# SCH_TH_RGB_LED_Stick_2022-05-16.net
KiCad netlist of a schematic drawn in EasyEDA
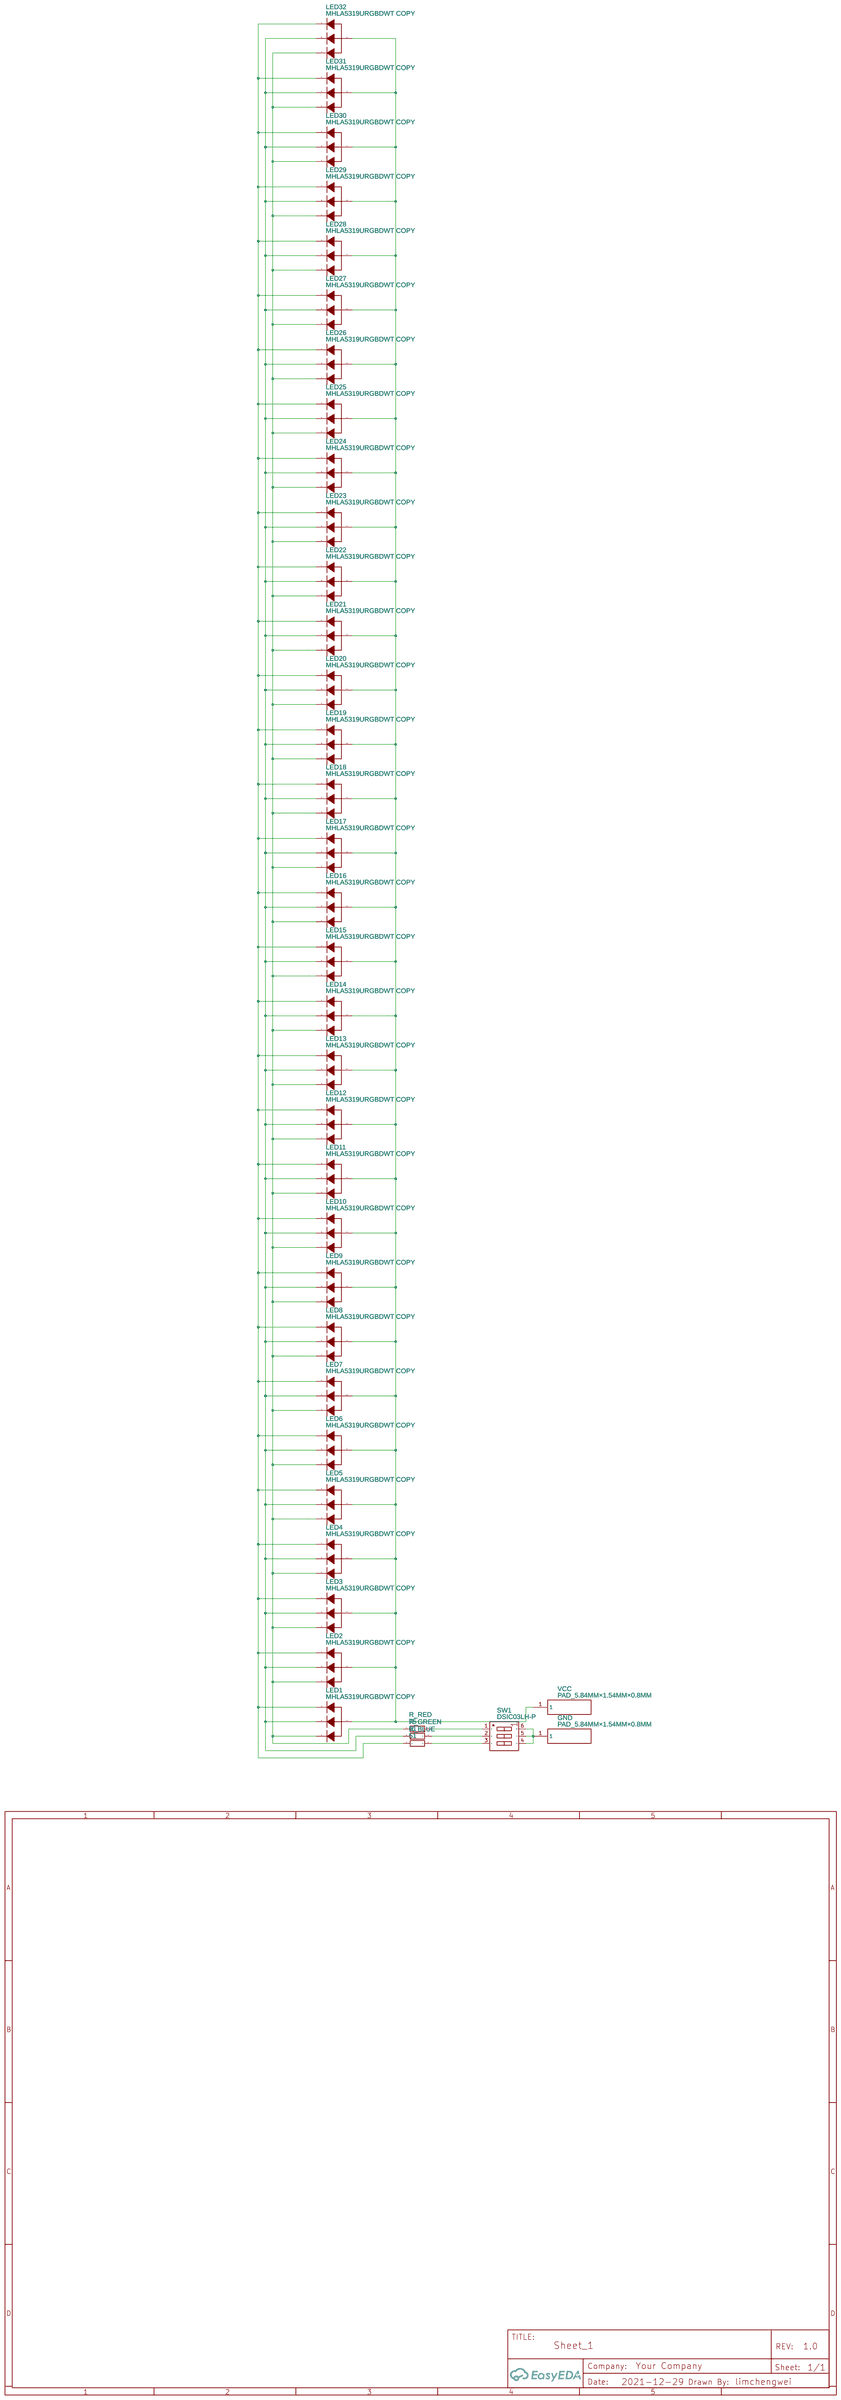
[diagram p0: schematic sheet]

(export (version "E")
  (design (tool "Eeschema 10.0.6"))
  (components
    (comp (ref "GND")
      (value "PAD_5.84MM×1.54MM×0.8MM")
      (fields
        (field (name "BOM_Manufacturer Part") "PAD_5.84mm×1.54mm×0.8mm")
        (field (name "BOM_Supplier Part") "C9900000335")
      )
      (libsource (lib "") (part "PAD_5.84MM×1.54MM×0.8MM_1"))
    )
    (comp (ref "LED1")
      (value "MHLA5319URGBDWT COPY")
      (fields
        (field (name "BOM_Manufacturer Part") "MHLA5319URGBDWT")
        (field (name "BOM_Supplier Part") "C417349")
      )
      (libsource (lib "") (part "MHLA5319URGBDWT COPY"))
    )
    (comp (ref "LED2")
      (value "MHLA5319URGBDWT COPY")
      (fields
        (field (name "BOM_Manufacturer Part") "MHLA5319URGBDWT")
        (field (name "BOM_Supplier Part") "C417349")
      )
      (libsource (lib "") (part "MHLA5319URGBDWT COPY"))
    )
    (comp (ref "LED3")
      (value "MHLA5319URGBDWT COPY")
      (fields
        (field (name "BOM_Manufacturer Part") "MHLA5319URGBDWT")
        (field (name "BOM_Supplier Part") "C417349")
      )
      (libsource (lib "") (part "MHLA5319URGBDWT COPY"))
    )
    (comp (ref "LED4")
      (value "MHLA5319URGBDWT COPY")
      (fields
        (field (name "BOM_Manufacturer Part") "MHLA5319URGBDWT")
        (field (name "BOM_Supplier Part") "C417349")
      )
      (libsource (lib "") (part "MHLA5319URGBDWT COPY"))
    )
    (comp (ref "LED5")
      (value "MHLA5319URGBDWT COPY")
      (fields
        (field (name "BOM_Manufacturer Part") "MHLA5319URGBDWT")
        (field (name "BOM_Supplier Part") "C417349")
      )
      (libsource (lib "") (part "MHLA5319URGBDWT COPY"))
    )
    (comp (ref "LED6")
      (value "MHLA5319URGBDWT COPY")
      (fields
        (field (name "BOM_Manufacturer Part") "MHLA5319URGBDWT")
        (field (name "BOM_Supplier Part") "C417349")
      )
      (libsource (lib "") (part "MHLA5319URGBDWT COPY"))
    )
    (comp (ref "LED7")
      (value "MHLA5319URGBDWT COPY")
      (fields
        (field (name "BOM_Manufacturer Part") "MHLA5319URGBDWT")
        (field (name "BOM_Supplier Part") "C417349")
      )
      (libsource (lib "") (part "MHLA5319URGBDWT COPY"))
    )
    (comp (ref "LED8")
      (value "MHLA5319URGBDWT COPY")
      (fields
        (field (name "BOM_Manufacturer Part") "MHLA5319URGBDWT")
        (field (name "BOM_Supplier Part") "C417349")
      )
      (libsource (lib "") (part "MHLA5319URGBDWT COPY"))
    )
    (comp (ref "LED9")
      (value "MHLA5319URGBDWT COPY")
      (fields
        (field (name "BOM_Manufacturer Part") "MHLA5319URGBDWT")
        (field (name "BOM_Supplier Part") "C417349")
      )
      (libsource (lib "") (part "MHLA5319URGBDWT COPY"))
    )
    (comp (ref "LED10")
      (value "MHLA5319URGBDWT COPY")
      (fields
        (field (name "BOM_Manufacturer Part") "MHLA5319URGBDWT")
        (field (name "BOM_Supplier Part") "C417349")
      )
      (libsource (lib "") (part "MHLA5319URGBDWT COPY"))
    )
    (comp (ref "LED11")
      (value "MHLA5319URGBDWT COPY")
      (fields
        (field (name "BOM_Manufacturer Part") "MHLA5319URGBDWT")
        (field (name "BOM_Supplier Part") "C417349")
      )
      (libsource (lib "") (part "MHLA5319URGBDWT COPY"))
    )
    (comp (ref "LED12")
      (value "MHLA5319URGBDWT COPY")
      (fields
        (field (name "BOM_Manufacturer Part") "MHLA5319URGBDWT")
        (field (name "BOM_Supplier Part") "C417349")
      )
      (libsource (lib "") (part "MHLA5319URGBDWT COPY"))
    )
    (comp (ref "LED13")
      (value "MHLA5319URGBDWT COPY")
      (fields
        (field (name "BOM_Manufacturer Part") "MHLA5319URGBDWT")
        (field (name "BOM_Supplier Part") "C417349")
      )
      (libsource (lib "") (part "MHLA5319URGBDWT COPY"))
    )
    (comp (ref "LED14")
      (value "MHLA5319URGBDWT COPY")
      (fields
        (field (name "BOM_Manufacturer Part") "MHLA5319URGBDWT")
        (field (name "BOM_Supplier Part") "C417349")
      )
      (libsource (lib "") (part "MHLA5319URGBDWT COPY"))
    )
    (comp (ref "LED15")
      (value "MHLA5319URGBDWT COPY")
      (fields
        (field (name "BOM_Manufacturer Part") "MHLA5319URGBDWT")
        (field (name "BOM_Supplier Part") "C417349")
      )
      (libsource (lib "") (part "MHLA5319URGBDWT COPY"))
    )
    (comp (ref "LED16")
      (value "MHLA5319URGBDWT COPY")
      (fields
        (field (name "BOM_Manufacturer Part") "MHLA5319URGBDWT")
        (field (name "BOM_Supplier Part") "C417349")
      )
      (libsource (lib "") (part "MHLA5319URGBDWT COPY"))
    )
    (comp (ref "LED17")
      (value "MHLA5319URGBDWT COPY")
      (fields
        (field (name "BOM_Manufacturer Part") "MHLA5319URGBDWT")
        (field (name "BOM_Supplier Part") "C417349")
      )
      (libsource (lib "") (part "MHLA5319URGBDWT COPY"))
    )
    (comp (ref "LED18")
      (value "MHLA5319URGBDWT COPY")
      (fields
        (field (name "BOM_Manufacturer Part") "MHLA5319URGBDWT")
        (field (name "BOM_Supplier Part") "C417349")
      )
      (libsource (lib "") (part "MHLA5319URGBDWT COPY"))
    )
    (comp (ref "LED19")
      (value "MHLA5319URGBDWT COPY")
      (fields
        (field (name "BOM_Manufacturer Part") "MHLA5319URGBDWT")
        (field (name "BOM_Supplier Part") "C417349")
      )
      (libsource (lib "") (part "MHLA5319URGBDWT COPY"))
    )
    (comp (ref "LED20")
      (value "MHLA5319URGBDWT COPY")
      (fields
        (field (name "BOM_Manufacturer Part") "MHLA5319URGBDWT")
        (field (name "BOM_Supplier Part") "C417349")
      )
      (libsource (lib "") (part "MHLA5319URGBDWT COPY"))
    )
    (comp (ref "LED21")
      (value "MHLA5319URGBDWT COPY")
      (fields
        (field (name "BOM_Manufacturer Part") "MHLA5319URGBDWT")
        (field (name "BOM_Supplier Part") "C417349")
      )
      (libsource (lib "") (part "MHLA5319URGBDWT COPY"))
    )
    (comp (ref "LED22")
      (value "MHLA5319URGBDWT COPY")
      (fields
        (field (name "BOM_Manufacturer Part") "MHLA5319URGBDWT")
        (field (name "BOM_Supplier Part") "C417349")
      )
      (libsource (lib "") (part "MHLA5319URGBDWT COPY"))
    )
    (comp (ref "LED23")
      (value "MHLA5319URGBDWT COPY")
      (fields
        (field (name "BOM_Manufacturer Part") "MHLA5319URGBDWT")
        (field (name "BOM_Supplier Part") "C417349")
      )
      (libsource (lib "") (part "MHLA5319URGBDWT COPY"))
    )
    (comp (ref "LED24")
      (value "MHLA5319URGBDWT COPY")
      (fields
        (field (name "BOM_Manufacturer Part") "MHLA5319URGBDWT")
        (field (name "BOM_Supplier Part") "C417349")
      )
      (libsource (lib "") (part "MHLA5319URGBDWT COPY"))
    )
    (comp (ref "LED25")
      (value "MHLA5319URGBDWT COPY")
      (fields
        (field (name "BOM_Manufacturer Part") "MHLA5319URGBDWT")
        (field (name "BOM_Supplier Part") "C417349")
      )
      (libsource (lib "") (part "MHLA5319URGBDWT COPY"))
    )
    (comp (ref "LED26")
      (value "MHLA5319URGBDWT COPY")
      (fields
        (field (name "BOM_Manufacturer Part") "MHLA5319URGBDWT")
        (field (name "BOM_Supplier Part") "C417349")
      )
      (libsource (lib "") (part "MHLA5319URGBDWT COPY"))
    )
    (comp (ref "LED27")
      (value "MHLA5319URGBDWT COPY")
      (fields
        (field (name "BOM_Manufacturer Part") "MHLA5319URGBDWT")
        (field (name "BOM_Supplier Part") "C417349")
      )
      (libsource (lib "") (part "MHLA5319URGBDWT COPY"))
    )
    (comp (ref "LED28")
      (value "MHLA5319URGBDWT COPY")
      (fields
        (field (name "BOM_Manufacturer Part") "MHLA5319URGBDWT")
        (field (name "BOM_Supplier Part") "C417349")
      )
      (libsource (lib "") (part "MHLA5319URGBDWT COPY"))
    )
    (comp (ref "LED29")
      (value "MHLA5319URGBDWT COPY")
      (fields
        (field (name "BOM_Manufacturer Part") "MHLA5319URGBDWT")
        (field (name "BOM_Supplier Part") "C417349")
      )
      (libsource (lib "") (part "MHLA5319URGBDWT COPY"))
    )
    (comp (ref "LED30")
      (value "MHLA5319URGBDWT COPY")
      (fields
        (field (name "BOM_Manufacturer Part") "MHLA5319URGBDWT")
        (field (name "BOM_Supplier Part") "C417349")
      )
      (libsource (lib "") (part "MHLA5319URGBDWT COPY"))
    )
    (comp (ref "LED31")
      (value "MHLA5319URGBDWT COPY")
      (fields
        (field (name "BOM_Manufacturer Part") "MHLA5319URGBDWT")
        (field (name "BOM_Supplier Part") "C417349")
      )
      (libsource (lib "") (part "MHLA5319URGBDWT COPY"))
    )
    (comp (ref "LED32")
      (value "MHLA5319URGBDWT COPY")
      (fields
        (field (name "BOM_Manufacturer Part") "MHLA5319URGBDWT")
        (field (name "BOM_Supplier Part") "C417349")
      )
      (libsource (lib "") (part "MHLA5319URGBDWT COPY"))
    )
    (comp (ref "R_BLUE")
      (value "51")
      (fields (field (name "BOM_Supplier Part") "C119319"))
      (libsource (lib "") (part "MF1/4W-620Ω±1% T52_2"))
    )
    (comp (ref "R_GREEN")
      (value "51")
      (fields (field (name "BOM_Supplier Part") "C119319"))
      (libsource (lib "") (part "MF1/4W-620Ω±1% T52"))
    )
    (comp (ref "R_RED")
      (value "75")
      (fields (field (name "BOM_Supplier Part") "C119319"))
      (libsource (lib "") (part "MF1/4W-620Ω±1% T52_1"))
    )
    (comp (ref "SW1")
      (value "DSIC03LH-P")
      (fields (field (name "BOM_Supplier Part") "C319041"))
      (libsource (lib "") (part "DSIC03LH-P"))
    )
    (comp (ref "VCC")
      (value "PAD_5.84MM×1.54MM×0.8MM")
      (fields
        (field (name "BOM_Manufacturer Part") "PAD_5.84mm×1.54mm×0.8mm")
        (field (name "BOM_Supplier Part") "C9900000335")
      )
      (libsource (lib "") (part "PAD_5.84MM×1.54MM×0.8MM"))
    )
  )
  (nets
    (net (code "1") (name "Net-(LED1-+)") (class "Default")
      (node (ref "LED1") (pin "2") (pinfunction "+_2") (pintype "unspecified"))
      (node (ref "LED10") (pin "2") (pinfunction "+_2") (pintype "unspecified"))
      (node (ref "LED11") (pin "2") (pinfunction "+_2") (pintype "unspecified"))
      (node (ref "LED12") (pin "2") (pinfunction "+_2") (pintype "unspecified"))
      (node (ref "LED13") (pin "2") (pinfunction "+_2") (pintype "unspecified"))
      (node (ref "LED14") (pin "2") (pinfunction "+_2") (pintype "unspecified"))
      (node (ref "LED15") (pin "2") (pinfunction "+_2") (pintype "unspecified"))
      (node (ref "LED16") (pin "2") (pinfunction "+_2") (pintype "unspecified"))
      (node (ref "LED17") (pin "2") (pinfunction "+_2") (pintype "unspecified"))
      (node (ref "LED18") (pin "2") (pinfunction "+_2") (pintype "unspecified"))
      (node (ref "LED19") (pin "2") (pinfunction "+_2") (pintype "unspecified"))
      (node (ref "LED2") (pin "2") (pinfunction "+_2") (pintype "unspecified"))
      (node (ref "LED20") (pin "2") (pinfunction "+_2") (pintype "unspecified"))
      (node (ref "LED21") (pin "2") (pinfunction "+_2") (pintype "unspecified"))
      (node (ref "LED22") (pin "2") (pinfunction "+_2") (pintype "unspecified"))
      (node (ref "LED23") (pin "2") (pinfunction "+_2") (pintype "unspecified"))
      (node (ref "LED24") (pin "2") (pinfunction "+_2") (pintype "unspecified"))
      (node (ref "LED25") (pin "2") (pinfunction "+_2") (pintype "unspecified"))
      (node (ref "LED26") (pin "2") (pinfunction "+_2") (pintype "unspecified"))
      (node (ref "LED27") (pin "2") (pinfunction "+_2") (pintype "unspecified"))
      (node (ref "LED28") (pin "2") (pinfunction "+_2") (pintype "unspecified"))
      (node (ref "LED29") (pin "2") (pinfunction "+_2") (pintype "unspecified"))
      (node (ref "LED3") (pin "2") (pinfunction "+_2") (pintype "unspecified"))
      (node (ref "LED30") (pin "2") (pinfunction "+_2") (pintype "unspecified"))
      (node (ref "LED31") (pin "2") (pinfunction "+_2") (pintype "unspecified"))
      (node (ref "LED32") (pin "2") (pinfunction "+_2") (pintype "unspecified"))
      (node (ref "LED4") (pin "2") (pinfunction "+_2") (pintype "unspecified"))
      (node (ref "LED5") (pin "2") (pinfunction "+_2") (pintype "unspecified"))
      (node (ref "LED6") (pin "2") (pinfunction "+_2") (pintype "unspecified"))
      (node (ref "LED7") (pin "2") (pinfunction "+_2") (pintype "unspecified"))
      (node (ref "LED8") (pin "2") (pinfunction "+_2") (pintype "unspecified"))
      (node (ref "LED9") (pin "2") (pinfunction "+_2") (pintype "unspecified"))
      (node (ref "VCC") (pin "1") (pinfunction "1_1") (pintype "unspecified"))
    )
    (net (code "2") (name "Net-(LED1---Pad1)") (class "Default")
      (node (ref "LED1") (pin "1") (pinfunction "-_1") (pintype "unspecified"))
      (node (ref "LED10") (pin "1") (pinfunction "-_1") (pintype "unspecified"))
      (node (ref "LED11") (pin "1") (pinfunction "-_1") (pintype "unspecified"))
      (node (ref "LED12") (pin "1") (pinfunction "-_1") (pintype "unspecified"))
      (node (ref "LED13") (pin "1") (pinfunction "-_1") (pintype "unspecified"))
      (node (ref "LED14") (pin "1") (pinfunction "-_1") (pintype "unspecified"))
      (node (ref "LED15") (pin "1") (pinfunction "-_1") (pintype "unspecified"))
      (node (ref "LED16") (pin "1") (pinfunction "-_1") (pintype "unspecified"))
      (node (ref "LED17") (pin "1") (pinfunction "-_1") (pintype "unspecified"))
      (node (ref "LED18") (pin "1") (pinfunction "-_1") (pintype "unspecified"))
      (node (ref "LED19") (pin "1") (pinfunction "-_1") (pintype "unspecified"))
      (node (ref "LED2") (pin "1") (pinfunction "-_1") (pintype "unspecified"))
      (node (ref "LED20") (pin "1") (pinfunction "-_1") (pintype "unspecified"))
      (node (ref "LED21") (pin "1") (pinfunction "-_1") (pintype "unspecified"))
      (node (ref "LED22") (pin "1") (pinfunction "-_1") (pintype "unspecified"))
      (node (ref "LED23") (pin "1") (pinfunction "-_1") (pintype "unspecified"))
      (node (ref "LED24") (pin "1") (pinfunction "-_1") (pintype "unspecified"))
      (node (ref "LED25") (pin "1") (pinfunction "-_1") (pintype "unspecified"))
      (node (ref "LED26") (pin "1") (pinfunction "-_1") (pintype "unspecified"))
      (node (ref "LED27") (pin "1") (pinfunction "-_1") (pintype "unspecified"))
      (node (ref "LED28") (pin "1") (pinfunction "-_1") (pintype "unspecified"))
      (node (ref "LED29") (pin "1") (pinfunction "-_1") (pintype "unspecified"))
      (node (ref "LED3") (pin "1") (pinfunction "-_1") (pintype "unspecified"))
      (node (ref "LED30") (pin "1") (pinfunction "-_1") (pintype "unspecified"))
      (node (ref "LED31") (pin "1") (pinfunction "-_1") (pintype "unspecified"))
      (node (ref "LED32") (pin "1") (pinfunction "-_1") (pintype "unspecified"))
      (node (ref "LED4") (pin "1") (pinfunction "-_1") (pintype "unspecified"))
      (node (ref "LED5") (pin "1") (pinfunction "-_1") (pintype "unspecified"))
      (node (ref "LED6") (pin "1") (pinfunction "-_1") (pintype "unspecified"))
      (node (ref "LED7") (pin "1") (pinfunction "-_1") (pintype "unspecified"))
      (node (ref "LED8") (pin "1") (pinfunction "-_1") (pintype "unspecified"))
      (node (ref "LED9") (pin "1") (pinfunction "-_1") (pintype "unspecified"))
      (node (ref "R_RED") (pin "2") (pinfunction "2_2") (pintype "unspecified"))
    )
    (net (code "3") (name "Net-(LED1---Pad3)") (class "Default")
      (node (ref "LED1") (pin "3") (pinfunction "-_3") (pintype "unspecified"))
      (node (ref "LED10") (pin "3") (pinfunction "-_3") (pintype "unspecified"))
      (node (ref "LED11") (pin "3") (pinfunction "-_3") (pintype "unspecified"))
      (node (ref "LED12") (pin "3") (pinfunction "-_3") (pintype "unspecified"))
      (node (ref "LED13") (pin "3") (pinfunction "-_3") (pintype "unspecified"))
      (node (ref "LED14") (pin "3") (pinfunction "-_3") (pintype "unspecified"))
      (node (ref "LED15") (pin "3") (pinfunction "-_3") (pintype "unspecified"))
      (node (ref "LED16") (pin "3") (pinfunction "-_3") (pintype "unspecified"))
      (node (ref "LED17") (pin "3") (pinfunction "-_3") (pintype "unspecified"))
      (node (ref "LED18") (pin "3") (pinfunction "-_3") (pintype "unspecified"))
      (node (ref "LED19") (pin "3") (pinfunction "-_3") (pintype "unspecified"))
      (node (ref "LED2") (pin "3") (pinfunction "-_3") (pintype "unspecified"))
      (node (ref "LED20") (pin "3") (pinfunction "-_3") (pintype "unspecified"))
      (node (ref "LED21") (pin "3") (pinfunction "-_3") (pintype "unspecified"))
      (node (ref "LED22") (pin "3") (pinfunction "-_3") (pintype "unspecified"))
      (node (ref "LED23") (pin "3") (pinfunction "-_3") (pintype "unspecified"))
      (node (ref "LED24") (pin "3") (pinfunction "-_3") (pintype "unspecified"))
      (node (ref "LED25") (pin "3") (pinfunction "-_3") (pintype "unspecified"))
      (node (ref "LED26") (pin "3") (pinfunction "-_3") (pintype "unspecified"))
      (node (ref "LED27") (pin "3") (pinfunction "-_3") (pintype "unspecified"))
      (node (ref "LED28") (pin "3") (pinfunction "-_3") (pintype "unspecified"))
      (node (ref "LED29") (pin "3") (pinfunction "-_3") (pintype "unspecified"))
      (node (ref "LED3") (pin "3") (pinfunction "-_3") (pintype "unspecified"))
      (node (ref "LED30") (pin "3") (pinfunction "-_3") (pintype "unspecified"))
      (node (ref "LED31") (pin "3") (pinfunction "-_3") (pintype "unspecified"))
      (node (ref "LED32") (pin "3") (pinfunction "-_3") (pintype "unspecified"))
      (node (ref "LED4") (pin "3") (pinfunction "-_3") (pintype "unspecified"))
      (node (ref "LED5") (pin "3") (pinfunction "-_3") (pintype "unspecified"))
      (node (ref "LED6") (pin "3") (pinfunction "-_3") (pintype "unspecified"))
      (node (ref "LED7") (pin "3") (pinfunction "-_3") (pintype "unspecified"))
      (node (ref "LED8") (pin "3") (pinfunction "-_3") (pintype "unspecified"))
      (node (ref "LED9") (pin "3") (pinfunction "-_3") (pintype "unspecified"))
      (node (ref "R_GREEN") (pin "2") (pinfunction "2_2") (pintype "unspecified"))
    )
    (net (code "4") (name "Net-(LED1---Pad4)") (class "Default")
      (node (ref "LED1") (pin "4") (pinfunction "-_4") (pintype "unspecified"))
      (node (ref "LED10") (pin "4") (pinfunction "-_4") (pintype "unspecified"))
      (node (ref "LED11") (pin "4") (pinfunction "-_4") (pintype "unspecified"))
      (node (ref "LED12") (pin "4") (pinfunction "-_4") (pintype "unspecified"))
      (node (ref "LED13") (pin "4") (pinfunction "-_4") (pintype "unspecified"))
      (node (ref "LED14") (pin "4") (pinfunction "-_4") (pintype "unspecified"))
      (node (ref "LED15") (pin "4") (pinfunction "-_4") (pintype "unspecified"))
      (node (ref "LED16") (pin "4") (pinfunction "-_4") (pintype "unspecified"))
      (node (ref "LED17") (pin "4") (pinfunction "-_4") (pintype "unspecified"))
      (node (ref "LED18") (pin "4") (pinfunction "-_4") (pintype "unspecified"))
      (node (ref "LED19") (pin "4") (pinfunction "-_4") (pintype "unspecified"))
      (node (ref "LED2") (pin "4") (pinfunction "-_4") (pintype "unspecified"))
      (node (ref "LED20") (pin "4") (pinfunction "-_4") (pintype "unspecified"))
      (node (ref "LED21") (pin "4") (pinfunction "-_4") (pintype "unspecified"))
      (node (ref "LED22") (pin "4") (pinfunction "-_4") (pintype "unspecified"))
      (node (ref "LED23") (pin "4") (pinfunction "-_4") (pintype "unspecified"))
      (node (ref "LED24") (pin "4") (pinfunction "-_4") (pintype "unspecified"))
      (node (ref "LED25") (pin "4") (pinfunction "-_4") (pintype "unspecified"))
      (node (ref "LED26") (pin "4") (pinfunction "-_4") (pintype "unspecified"))
      (node (ref "LED27") (pin "4") (pinfunction "-_4") (pintype "unspecified"))
      (node (ref "LED28") (pin "4") (pinfunction "-_4") (pintype "unspecified"))
      (node (ref "LED29") (pin "4") (pinfunction "-_4") (pintype "unspecified"))
      (node (ref "LED3") (pin "4") (pinfunction "-_4") (pintype "unspecified"))
      (node (ref "LED30") (pin "4") (pinfunction "-_4") (pintype "unspecified"))
      (node (ref "LED31") (pin "4") (pinfunction "-_4") (pintype "unspecified"))
      (node (ref "LED32") (pin "4") (pinfunction "-_4") (pintype "unspecified"))
      (node (ref "LED4") (pin "4") (pinfunction "-_4") (pintype "unspecified"))
      (node (ref "LED5") (pin "4") (pinfunction "-_4") (pintype "unspecified"))
      (node (ref "LED6") (pin "4") (pinfunction "-_4") (pintype "unspecified"))
      (node (ref "LED7") (pin "4") (pinfunction "-_4") (pintype "unspecified"))
      (node (ref "LED8") (pin "4") (pinfunction "-_4") (pintype "unspecified"))
      (node (ref "LED9") (pin "4") (pinfunction "-_4") (pintype "unspecified"))
      (node (ref "R_BLUE") (pin "2") (pinfunction "2_2") (pintype "unspecified"))
    )
    (net (code "5") (name "Net-(SW1-PIN1)") (class "Default")
      (node (ref "R_RED") (pin "1") (pinfunction "1_1") (pintype "unspecified"))
      (node (ref "SW1") (pin "1") (pinfunction "PIN1_1") (pintype "unspecified"))
    )
    (net (code "6") (name "Net-(SW1-PIN2)") (class "Default")
      (node (ref "R_GREEN") (pin "1") (pinfunction "1_1") (pintype "unspecified"))
      (node (ref "SW1") (pin "2") (pinfunction "PIN2_2") (pintype "unspecified"))
    )
    (net (code "7") (name "Net-(SW1-PIN3)") (class "Default")
      (node (ref "R_BLUE") (pin "1") (pinfunction "1_1") (pintype "unspecified"))
      (node (ref "SW1") (pin "3") (pinfunction "PIN3_3") (pintype "unspecified"))
    )
    (net (code "8") (name "Net-(SW1-PIN4)") (class "Default")
      (node (ref "GND") (pin "1") (pinfunction "1_1") (pintype "unspecified"))
      (node (ref "SW1") (pin "4") (pinfunction "PIN4_4") (pintype "unspecified"))
      (node (ref "SW1") (pin "5") (pinfunction "PIN5_5") (pintype "unspecified"))
      (node (ref "SW1") (pin "6") (pinfunction "PIN6_6") (pintype "unspecified"))
    )
  )
)
